# Fri3D_2020_Peripherals.net
KiCad netlist of a schematic drawn in Altium Designer
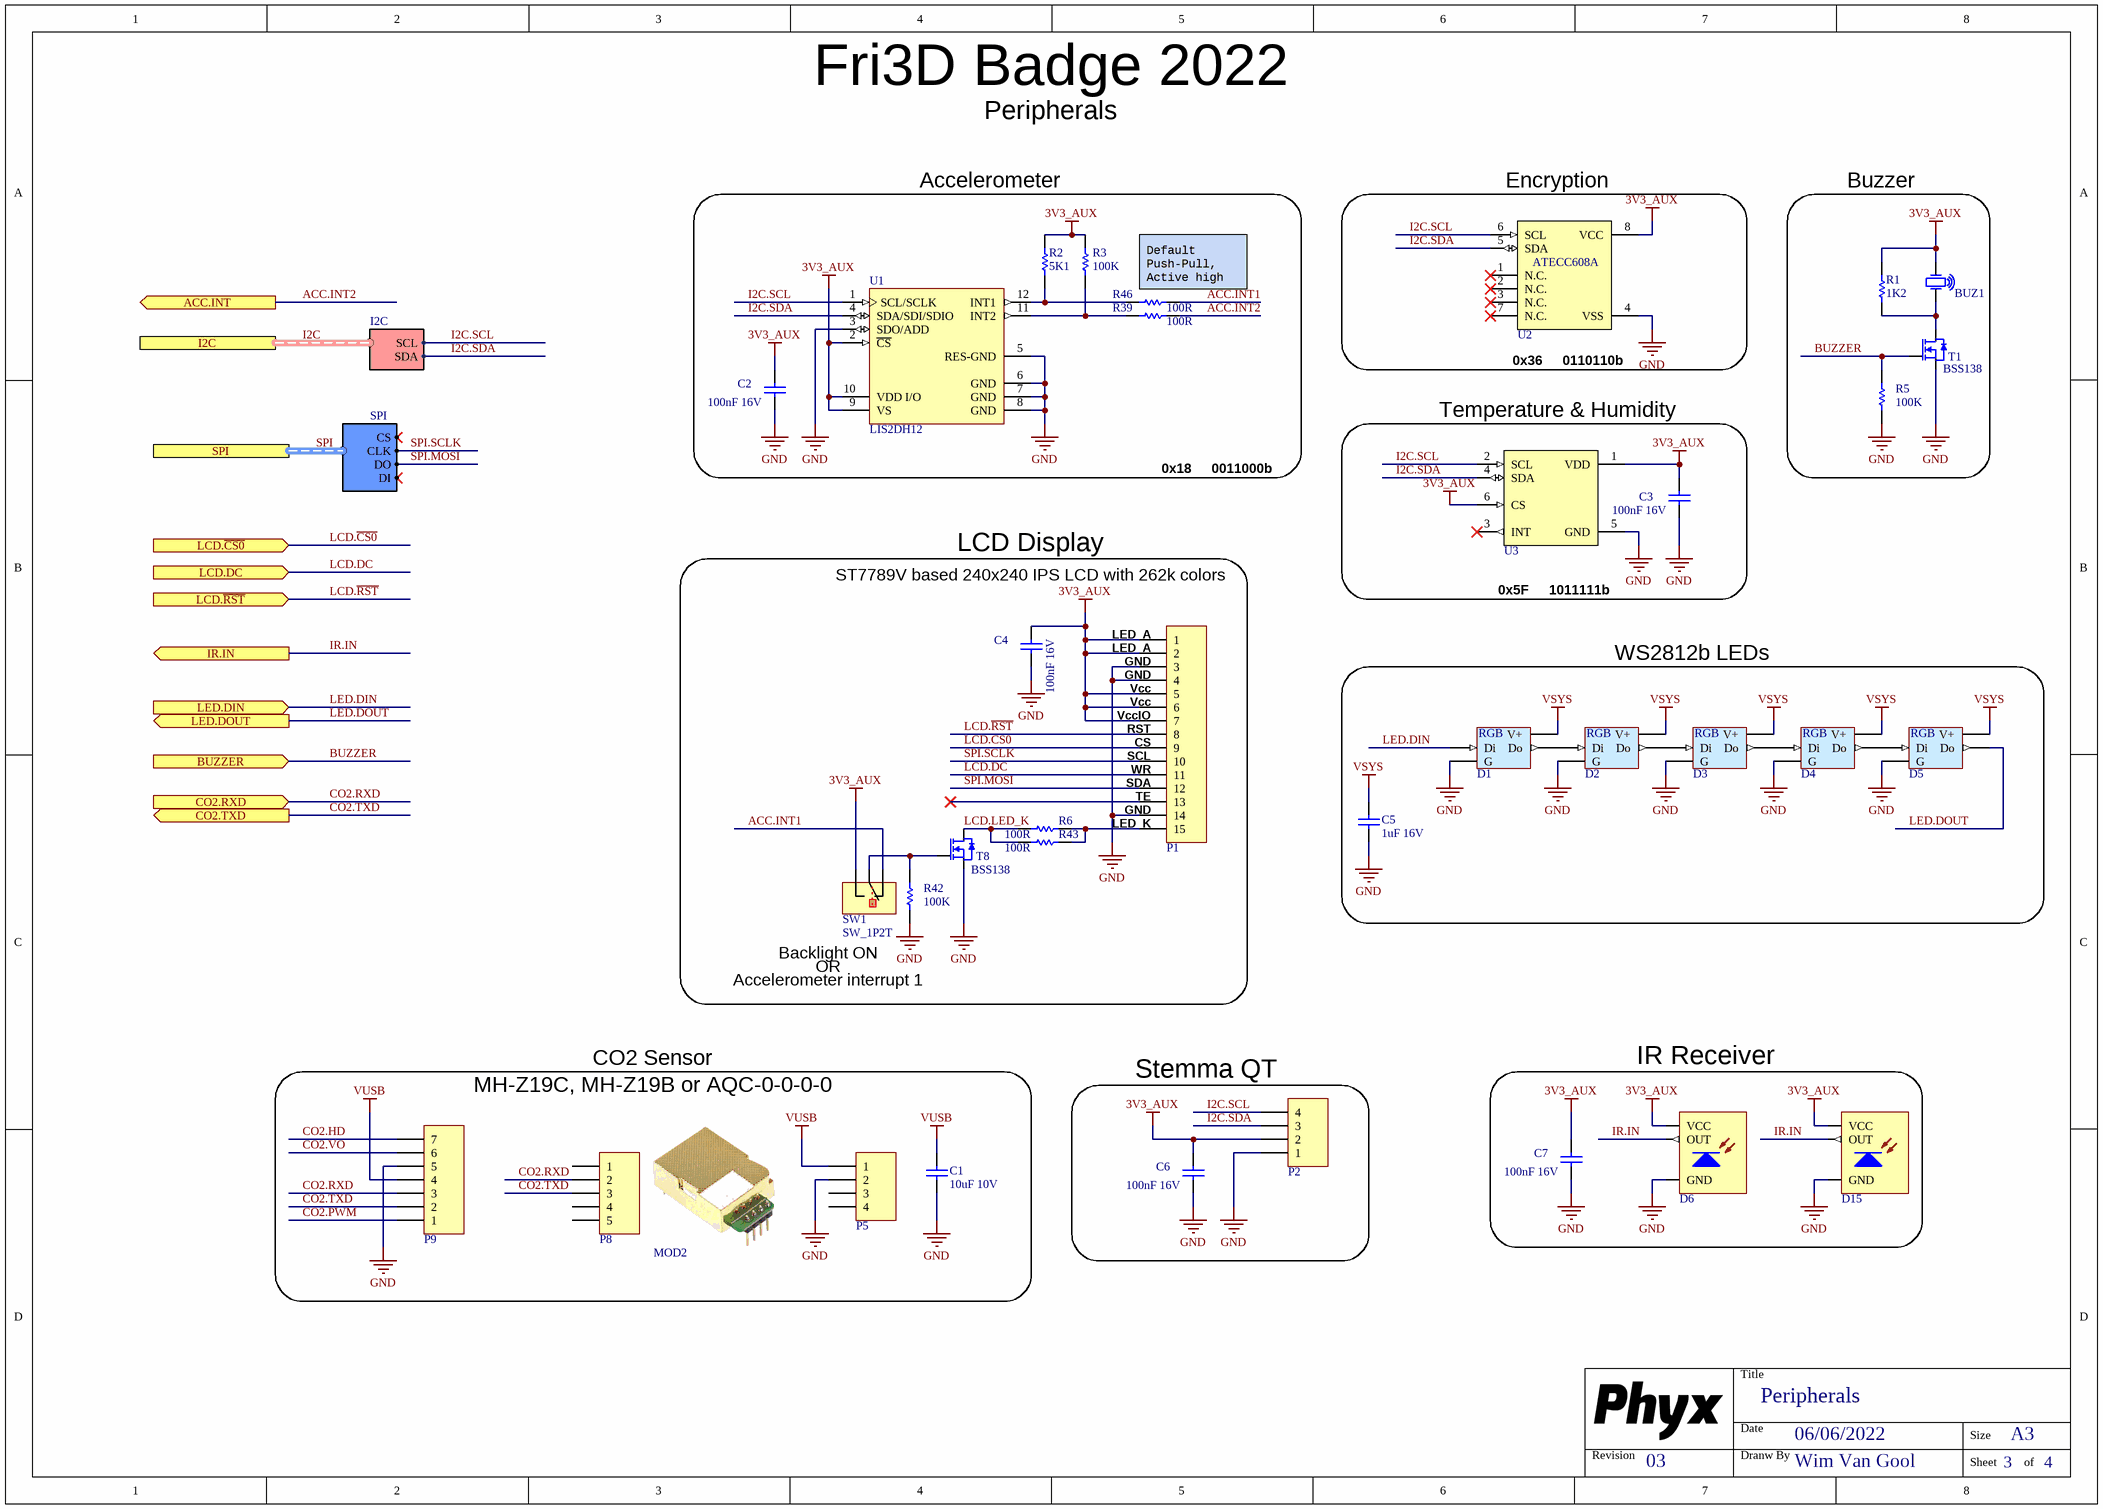
[diagram p0: Fri3D_2020_Peripherals.SchDoc]

(export (version "E")
  (design (tool "Eeschema 10.0.6"))
  (components
    (comp (ref "BUZ1")
      (value "12x12x3mm Piezo Buzzer Transducer 81dB")
      (footprint "CUI_CMT-1203-SMT")
      (description "Crystal Oscillator")
      (libsource (lib "Phyx_Components") (part "Buzzer"))
    )
    (comp (ref "C1")
      (value "10uF 10V")
      (footprint "C0805_N")
      (description "Capacitor Ceramic")
      (fields (field (name "Comment") "CAP_CERAMIC"))
      (libsource (lib "Phyx_Components") (part "CAP_CERAMIC"))
    )
    (comp (ref "C2")
      (value "100nF 16V")
      (footprint "C0603_N")
      (description "Capacitor Ceramic")
      (libsource (lib "Phyx_Components") (part "CAP_CERAMIC"))
    )
    (comp (ref "C3")
      (value "100nF 16V")
      (footprint "C0603_N")
      (description "Capacitor Ceramic")
      (libsource (lib "Phyx_Components") (part "CAP_CERAMIC"))
    )
    (comp (ref "C4")
      (value "100nF 16V")
      (footprint "C0603_N")
      (description "Capacitor Ceramic")
      (libsource (lib "Phyx_Components") (part "CAP_CERAMIC"))
    )
    (comp (ref "C5")
      (value "1uF 16V")
      (footprint "C0603_N")
      (description "Capacitor Ceramic")
      (fields (field (name "Comment") "CAP_CERAMIC"))
      (libsource (lib "Phyx_Components") (part "CAP_CERAMIC"))
    )
    (comp (ref "C6")
      (value "100nF 16V")
      (footprint "C0603_N")
      (description "Capacitor Ceramic")
      (libsource (lib "Phyx_Components") (part "CAP_CERAMIC"))
    )
    (comp (ref "C7")
      (value "100nF 16V")
      (footprint "C0603_N")
      (description "Capacitor Ceramic")
      (libsource (lib "Phyx_Components") (part "CAP_CERAMIC"))
    )
    (comp (ref "D1")
      (value "WS2812 based digital RGB LED 5050 Black package")
      (footprint "LED_5050_WS2812B_BLACK")
      (description "=Description")
      (libsource (lib "Phyx_Components") (part "LED_RGB_WS2812B_5050"))
    )
    (comp (ref "D2")
      (value "WS2812 based digital RGB LED 5050 Black package")
      (footprint "LED_5050_WS2812B_BLACK")
      (description "=Description")
      (libsource (lib "Phyx_Components") (part "LED_RGB_WS2812B_5050"))
    )
    (comp (ref "D3")
      (value "WS2812 based digital RGB LED 5050 Black package")
      (footprint "LED_5050_WS2812B_BLACK")
      (description "=Description")
      (libsource (lib "Phyx_Components") (part "LED_RGB_WS2812B_5050"))
    )
    (comp (ref "D4")
      (value "WS2812 based digital RGB LED 5050 Black package")
      (footprint "LED_5050_WS2812B_BLACK")
      (description "=Description")
      (libsource (lib "Phyx_Components") (part "LED_RGB_WS2812B_5050"))
    )
    (comp (ref "D5")
      (value "WS2812 based digital RGB LED 5050 Black package")
      (footprint "LED_5050_WS2812B_BLACK")
      (description "=Description")
      (libsource (lib "Phyx_Components") (part "LED_RGB_WS2812B_5050"))
    )
    (comp (ref "D6")
      (value "IRM-3638N3F14 Infrared Receiver 38 kHz 45° 2.7-5.5V")
      (footprint "VIS_TSOP381x_BENT")
      (description "=Description")
      (libsource (lib "Phyx_Components") (part "PHO_IR_TSOP381x"))
    )
    (comp (ref "D15")
      (value "ZIRM-5042B-42-Z2 Infrared Receiver 38 kHz 45° 2.7-5.5V 940nm")
      (footprint "CHAU_ZIRM-5042B-42-Z2")
      (description "=Description")
      (libsource (lib "Phyx_Components") (part "PHO_IR_TSOP381x"))
    )
    (comp (ref "MOD2")
      (value "MH-Z19C CO2 Sensor TH Pins")
      (footprint "WIN_MH-Z19x-PH")
      (description "Winsen MH-Z19x-PH series of CO2 sensors")
      (libsource (lib "Phyx_Components") (part "WIN_MH-Z19x-PH"))
    )
    (comp (ref "P1")
      (value "Bottom contact FPC 0.3mm pitch 15 contacts")
      (footprint "FPC_AFE03-S15FMA-1H")
      (libsource (lib "Phyx_Components") (part "Header 15"))
    )
    (comp (ref "P2")
      (value "Header 1.0mm RA Shrouded 4")
      (footprint "WE_665104131822")
      (libsource (lib "Phyx_Components") (part "Header 4"))
    )
    (comp (ref "P5")
      (value "Receptacle 4 SMD Type 2")
      (footprint "WE_61000413321")
      (libsource (lib "") (part "Header 4_1"))
    )
    (comp (ref "P8")
      (value "Receptacle 5 SMD Type 2")
      (footprint "WE_61000513321")
      (libsource (lib "Phyx_Components") (part "Header 5"))
    )
    (comp (ref "P9")
      (value "Molex Picoblade SMD RA 532610771")
      (footprint "MLX_53261-0771")
      (libsource (lib "Phyx_Components") (part "Header 7"))
    )
    (comp (ref "R1")
      (value "1K2")
      (footprint "R0603_N")
      (fields (field (name "Comment") "RESISTOR"))
      (libsource (lib "Phyx_Components") (part "RESISTOR"))
    )
    (comp (ref "R2")
      (value "5K1")
      (footprint "R0603_N")
      (fields (field (name "Comment") "RESISTOR"))
      (libsource (lib "Phyx_Components") (part "RESISTOR"))
    )
    (comp (ref "R3")
      (value "100K")
      (footprint "R0603_N")
      (fields (field (name "Comment") "RESISTOR"))
      (libsource (lib "Phyx_Components") (part "RESISTOR"))
    )
    (comp (ref "R5")
      (value "100K")
      (footprint "R0603_N")
      (fields (field (name "Comment") "RESISTOR"))
      (libsource (lib "Phyx_Components") (part "RESISTOR"))
    )
    (comp (ref "R6")
      (value "100R")
      (footprint "R0603_N")
      (fields (field (name "Comment") "RESISTOR"))
      (libsource (lib "Phyx_Components") (part "RESISTOR"))
    )
    (comp (ref "R39")
      (value "100R")
      (footprint "R0603_N")
      (fields (field (name "Comment") "RESISTOR"))
      (libsource (lib "Phyx_Components") (part "RESISTOR"))
    )
    (comp (ref "R42")
      (value "100K")
      (footprint "R0603_N")
      (fields (field (name "Comment") "RESISTOR"))
      (libsource (lib "Phyx_Components") (part "RESISTOR"))
    )
    (comp (ref "R43")
      (value "100R")
      (footprint "R0603_N")
      (fields (field (name "Comment") "RESISTOR"))
      (libsource (lib "Phyx_Components") (part "RESISTOR"))
    )
    (comp (ref "R46")
      (value "100R")
      (footprint "R0603_N")
      (fields (field (name "Comment") "RESISTOR"))
      (libsource (lib "Phyx_Components") (part "RESISTOR"))
    )
    (comp (ref "SW1")
      (value "SW_1P2T")
      (footprint "WE_450404015514")
      (libsource (lib "Phyx_Components") (part "SW_1P2T"))
    )
    (comp (ref "T1")
      (value "BSS138")
      (footprint "SOT23-3")
      (fields (field (name "Comment") "0.2A N-Ch MOSFET Vgs 3.2"))
      (libsource (lib "Phyx_Components") (part "N_MOSFET_GSD"))
    )
    (comp (ref "T8")
      (value "BSS138")
      (footprint "SOT23-3")
      (fields (field (name "Comment") "0.2A N-Ch MOSFET Vgs 3.2"))
      (libsource (lib "Phyx_Components") (part "N_MOSFET_GSD"))
    )
    (comp (ref "U1")
      (value "LIS2DH12")
      (footprint "STM_LGA12_2x2")
      (description "=Description")
      (libsource (lib "Phyx_Components") (part "STM_LIS2DH12"))
    )
    (comp (ref "U2")
      (value "Encryption Authentication with 72b SN, SHA-256, AES-128")
      (footprint "SOIC_N_8")
      (description "=Description")
      (libsource (lib "Phyx_Components") (part "ATECC608A-SSHDA"))
    )
    (comp (ref "U3")
      (value "WSEN-HIDS 2525020210001 temperature and humidity sensor Digital I2C")
      (footprint "WE_2525020210001")
      (description "=Description")
      (libsource (lib "Phyx_Components") (part "WE_2525020210001"))
    )
  )
  (nets
    (net (code "3") (name "/ACC.INT1") (class "Default")
      (node (ref "R46") (pin "2") (pinfunction "2_2") (pintype "passive"))
      (node (ref "SW1") (pin "1") (pinfunction "1_1") (pintype "passive"))
    )
    (net (code "4") (name "/ACC.INT2") (class "Default")
      (node (ref "R39") (pin "2") (pinfunction "2_2") (pintype "passive"))
    )
    (net (code "5") (name "/BUZZER") (class "Default")
      (node (ref "R5") (pin "1") (pinfunction "1_1") (pintype "passive"))
      (node (ref "T1") (pin "1") (pinfunction "G_1") (pintype "passive"))
    )
    (net (code "6") (name "/CO2.HD") (class "Default")
      (node (ref "P9") (pin "7") (pinfunction "7_7") (pintype "passive"))
    )
    (net (code "7") (name "/CO2.PWM") (class "Default")
      (node (ref "P9") (pin "1") (pinfunction "1_1") (pintype "passive"))
    )
    (net (code "8") (name "/CO2.RXD") (class "Default")
      (node (ref "P8") (pin "2") (pinfunction "2_2") (pintype "passive"))
      (node (ref "P9") (pin "3") (pinfunction "3_3") (pintype "passive"))
    )
    (net (code "9") (name "/CO2.TXD") (class "Default")
      (node (ref "P8") (pin "3") (pinfunction "3_3") (pintype "passive"))
      (node (ref "P9") (pin "2") (pinfunction "2_2") (pintype "passive"))
    )
    (net (code "10") (name "/CO2.VO") (class "Default")
      (node (ref "P9") (pin "6") (pinfunction "6_6") (pintype "passive"))
    )
    (net (code "11") (name "/I2C.SCL") (class "Default")
      (node (ref "P2") (pin "4") (pinfunction "4_4") (pintype "passive"))
      (node (ref "U1") (pin "1") (pinfunction "SCL/SCLK_1") (pintype "input"))
      (node (ref "U2") (pin "6") (pinfunction "SCL_6") (pintype "input"))
      (node (ref "U3") (pin "2") (pinfunction "SCL_2") (pintype "input"))
    )
    (net (code "12") (name "/I2C.SDA") (class "Default")
      (node (ref "P2") (pin "3") (pinfunction "3_3") (pintype "passive"))
      (node (ref "U1") (pin "4") (pinfunction "SDA/SDI/SDIO_4") (pintype "bidirectional"))
      (node (ref "U2") (pin "5") (pinfunction "SDA_5") (pintype "bidirectional"))
      (node (ref "U3") (pin "4") (pinfunction "SDA_4") (pintype "bidirectional"))
    )
    (net (code "14") (name "/IR.IN") (class "Default")
      (node (ref "D15") (pin "1") (pinfunction "OUT_1") (pintype "output"))
      (node (ref "D6") (pin "1") (pinfunction "OUT_1") (pintype "output"))
    )
    (net (code "15") (name "/LCD.DC") (class "Default")
      (node (ref "P1") (pin "11") (pinfunction "11_11") (pintype "passive"))
    )
    (net (code "16") (name "/LCD.LED_K") (class "Default")
      (node (ref "R43") (pin "2") (pinfunction "2_2") (pintype "passive"))
      (node (ref "R6") (pin "2") (pinfunction "2_2") (pintype "passive"))
      (node (ref "T8") (pin "3") (pinfunction "D_3") (pintype "passive"))
    )
    (net (code "17") (name "/LCD.~{CS0}") (class "Default")
      (node (ref "P1") (pin "9") (pinfunction "9_9") (pintype "passive"))
    )
    (net (code "18") (name "/LCD.~{RST}") (class "Default")
      (node (ref "P1") (pin "8") (pinfunction "8_8") (pintype "passive"))
    )
    (net (code "19") (name "/LED.DIN") (class "Default")
      (node (ref "D1") (pin "4") (pinfunction "Di_4") (pintype "input"))
    )
    (net (code "20") (name "/LED.DOUT") (class "Default")
      (node (ref "D5") (pin "2") (pinfunction "Do_2") (pintype "output"))
    )
    (net (code "21") (name "/SPI.MOSI") (class "Default")
      (node (ref "P1") (pin "12") (pinfunction "12_12") (pintype "passive"))
    )
    (net (code "22") (name "/SPI.SCLK") (class "Default")
      (node (ref "P1") (pin "10") (pinfunction "10_10") (pintype "passive"))
    )
    (net (code "24") (name "3V3_AUX") (class "Default")
      (node (ref "BUZ1") (pin "1") (pinfunction "OSC1_1") (pintype "passive"))
      (node (ref "C2") (pin "1") (pinfunction "1_1") (pintype "passive"))
      (node (ref "C3") (pin "1") (pinfunction "1_1") (pintype "passive"))
      (node (ref "C4") (pin "1") (pinfunction "1_1") (pintype "passive"))
      (node (ref "C6") (pin "1") (pinfunction "1_1") (pintype "passive"))
      (node (ref "C7") (pin "1") (pinfunction "1_1") (pintype "passive"))
      (node (ref "D15") (pin "3") (pinfunction "VCC_3") (pintype "power_in"))
      (node (ref "D6") (pin "3") (pinfunction "VCC_3") (pintype "power_in"))
      (node (ref "P1") (pin "1") (pinfunction "1_1") (pintype "passive"))
      (node (ref "P1") (pin "2") (pinfunction "2_2") (pintype "passive"))
      (node (ref "P1") (pin "5") (pinfunction "5_5") (pintype "passive"))
      (node (ref "P1") (pin "6") (pinfunction "6_6") (pintype "passive"))
      (node (ref "P1") (pin "7") (pinfunction "7_7") (pintype "passive"))
      (node (ref "P2") (pin "2") (pinfunction "2_2") (pintype "passive"))
      (node (ref "R1") (pin "1") (pinfunction "1_1") (pintype "passive"))
      (node (ref "R2") (pin "1") (pinfunction "1_1") (pintype "passive"))
      (node (ref "R3") (pin "1") (pinfunction "1_1") (pintype "passive"))
      (node (ref "SW1") (pin "3") (pinfunction "3_3") (pintype "passive"))
      (node (ref "U1") (pin "10") (pinfunction "VDD_I/O_10") (pintype "power_in"))
      (node (ref "U1") (pin "2") (pinfunction "~{CS}_2") (pintype "input"))
      (node (ref "U1") (pin "9") (pinfunction "VS_9") (pintype "power_in"))
      (node (ref "U2") (pin "8") (pinfunction "VCC_8") (pintype "power_in"))
      (node (ref "U3") (pin "1") (pinfunction "VDD_1") (pintype "power_in"))
      (node (ref "U3") (pin "6") (pinfunction "CS_6") (pintype "input"))
    )
    (net (code "25") (name "GND") (class "Default")
      (node (ref "C1") (pin "2") (pinfunction "2_2") (pintype "passive"))
      (node (ref "C2") (pin "2") (pinfunction "2_2") (pintype "passive"))
      (node (ref "C3") (pin "2") (pinfunction "2_2") (pintype "passive"))
      (node (ref "C4") (pin "2") (pinfunction "2_2") (pintype "passive"))
      (node (ref "C5") (pin "2") (pinfunction "2_2") (pintype "passive"))
      (node (ref "C6") (pin "2") (pinfunction "2_2") (pintype "passive"))
      (node (ref "C7") (pin "2") (pinfunction "2_2") (pintype "passive"))
      (node (ref "D1") (pin "3") (pinfunction "G_3") (pintype "power_in"))
      (node (ref "D15") (pin "2") (pinfunction "GND_2") (pintype "power_in"))
      (node (ref "D2") (pin "3") (pinfunction "G_3") (pintype "power_in"))
      (node (ref "D3") (pin "3") (pinfunction "G_3") (pintype "power_in"))
      (node (ref "D4") (pin "3") (pinfunction "G_3") (pintype "power_in"))
      (node (ref "D5") (pin "3") (pinfunction "G_3") (pintype "power_in"))
      (node (ref "D6") (pin "2") (pinfunction "GND_2") (pintype "power_in"))
      (node (ref "P1") (pin "14") (pinfunction "14_14") (pintype "passive"))
      (node (ref "P1") (pin "3") (pinfunction "3_3") (pintype "passive"))
      (node (ref "P1") (pin "4") (pinfunction "4_4") (pintype "passive"))
      (node (ref "P2") (pin "1") (pinfunction "1_1") (pintype "passive"))
      (node (ref "P5") (pin "2") (pinfunction "2_2") (pintype "passive"))
      (node (ref "P9") (pin "5") (pinfunction "5_5") (pintype "passive"))
      (node (ref "R42") (pin "2") (pinfunction "2_2") (pintype "passive"))
      (node (ref "R5") (pin "2") (pinfunction "2_2") (pintype "passive"))
      (node (ref "T1") (pin "2") (pinfunction "S_2") (pintype "passive"))
      (node (ref "T8") (pin "2") (pinfunction "S_2") (pintype "passive"))
      (node (ref "U1") (pin "3") (pinfunction "SDO/ADD_3") (pintype "bidirectional"))
      (node (ref "U1") (pin "5") (pinfunction "RES-GND_5") (pintype "passive"))
      (node (ref "U1") (pin "6") (pinfunction "GND_6") (pintype "power_in"))
      (node (ref "U1") (pin "7") (pinfunction "GND_7") (pintype "power_in"))
      (node (ref "U1") (pin "8") (pinfunction "GND_8") (pintype "power_in"))
      (node (ref "U2") (pin "4") (pinfunction "VSS_4") (pintype "power_in"))
      (node (ref "U3") (pin "5") (pinfunction "GND_5") (pintype "power_in"))
    )
    (net (code "26") (name "Net-(BUZ1-OSC2)") (class "Default")
      (node (ref "BUZ1") (pin "2") (pinfunction "OSC2_2") (pintype "passive"))
      (node (ref "R1") (pin "2") (pinfunction "2_2") (pintype "passive"))
      (node (ref "T1") (pin "3") (pinfunction "D_3") (pintype "passive"))
    )
    (net (code "27") (name "Net-(D1-Do)") (class "Default")
      (node (ref "D1") (pin "2") (pinfunction "Do_2") (pintype "output"))
      (node (ref "D2") (pin "4") (pinfunction "Di_4") (pintype "input"))
    )
    (net (code "28") (name "Net-(D2-Do)") (class "Default")
      (node (ref "D2") (pin "2") (pinfunction "Do_2") (pintype "output"))
      (node (ref "D3") (pin "4") (pinfunction "Di_4") (pintype "input"))
    )
    (net (code "29") (name "Net-(D3-Do)") (class "Default")
      (node (ref "D3") (pin "2") (pinfunction "Do_2") (pintype "output"))
      (node (ref "D4") (pin "4") (pinfunction "Di_4") (pintype "input"))
    )
    (net (code "30") (name "Net-(D4-Do)") (class "Default")
      (node (ref "D4") (pin "2") (pinfunction "Do_2") (pintype "output"))
      (node (ref "D5") (pin "4") (pinfunction "Di_4") (pintype "input"))
    )
    (net (code "31") (name "Net-(P1-Pad15)") (class "Default")
      (node (ref "P1") (pin "15") (pinfunction "15_15") (pintype "passive"))
      (node (ref "R43") (pin "1") (pinfunction "1_1") (pintype "passive"))
      (node (ref "R6") (pin "1") (pinfunction "1_1") (pintype "passive"))
    )
    (net (code "32") (name "Net-(T8-G)") (class "Default")
      (node (ref "R42") (pin "1") (pinfunction "1_1") (pintype "passive"))
      (node (ref "SW1") (pin "2") (pinfunction "2_2") (pintype "passive"))
      (node (ref "T8") (pin "1") (pinfunction "G_1") (pintype "passive"))
    )
    (net (code "33") (name "Net-(U1-INT1)") (class "Default")
      (node (ref "R2") (pin "2") (pinfunction "2_2") (pintype "passive"))
      (node (ref "R46") (pin "1") (pinfunction "1_1") (pintype "passive"))
      (node (ref "U1") (pin "12") (pinfunction "INT1_12") (pintype "output"))
    )
    (net (code "34") (name "Net-(U1-INT2)") (class "Default")
      (node (ref "R3") (pin "2") (pinfunction "2_2") (pintype "passive"))
      (node (ref "R39") (pin "1") (pinfunction "1_1") (pintype "passive"))
      (node (ref "U1") (pin "11") (pinfunction "INT2_11") (pintype "output"))
    )
    (net (code "35") (name "VSYS") (class "Default")
      (node (ref "C5") (pin "1") (pinfunction "1_1") (pintype "passive"))
      (node (ref "D1") (pin "1") (pinfunction "V+_1") (pintype "power_in"))
      (node (ref "D2") (pin "1") (pinfunction "V+_1") (pintype "power_in"))
      (node (ref "D3") (pin "1") (pinfunction "V+_1") (pintype "power_in"))
      (node (ref "D4") (pin "1") (pinfunction "V+_1") (pintype "power_in"))
      (node (ref "D5") (pin "1") (pinfunction "V+_1") (pintype "power_in"))
    )
    (net (code "36") (name "VUSB") (class "Default")
      (node (ref "C1") (pin "1") (pinfunction "1_1") (pintype "passive"))
      (node (ref "P5") (pin "1") (pinfunction "1_1") (pintype "passive"))
      (node (ref "P9") (pin "4") (pinfunction "4_4") (pintype "passive"))
    )
    (net (code "37") (name "unconnected-(P1-Pad13)") (class "Default")
      (node (ref "P1") (pin "13") (pinfunction "13_13") (pintype "passive+no_connect"))
    )
    (net (code "38") (name "unconnected-(P5-Pad3)") (class "Default")
      (node (ref "P5") (pin "3") (pinfunction "3_3") (pintype "passive"))
    )
    (net (code "39") (name "unconnected-(P5-Pad4)") (class "Default")
      (node (ref "P5") (pin "4") (pinfunction "4_4") (pintype "passive"))
    )
    (net (code "40") (name "unconnected-(P8-Pad1)") (class "Default")
      (node (ref "P8") (pin "1") (pinfunction "1_1") (pintype "passive"))
    )
    (net (code "41") (name "unconnected-(P8-Pad4)") (class "Default")
      (node (ref "P8") (pin "4") (pinfunction "4_4") (pintype "passive"))
    )
    (net (code "42") (name "unconnected-(P8-Pad5)") (class "Default")
      (node (ref "P8") (pin "5") (pinfunction "5_5") (pintype "passive"))
    )
    (net (code "43") (name "unconnected-(U2-N.C.-Pad1)") (class "Default")
      (node (ref "U2") (pin "1") (pinfunction "N.C._1") (pintype "passive+no_connect"))
    )
    (net (code "44") (name "unconnected-(U2-N.C.-Pad2)") (class "Default")
      (node (ref "U2") (pin "2") (pinfunction "N.C._2") (pintype "passive+no_connect"))
    )
    (net (code "45") (name "unconnected-(U2-N.C.-Pad3)") (class "Default")
      (node (ref "U2") (pin "3") (pinfunction "N.C._3") (pintype "passive+no_connect"))
    )
    (net (code "46") (name "unconnected-(U2-N.C.-Pad7)") (class "Default")
      (node (ref "U2") (pin "7") (pinfunction "N.C._7") (pintype "passive+no_connect"))
    )
    (net (code "47") (name "unconnected-(U3-INT-Pad3)") (class "Default")
      (node (ref "U3") (pin "3") (pinfunction "INT_3") (pintype "output+no_connect"))
    )
  )
)
